# RGBdriver.net
KiCad netlist of a schematic drawn in EAGLE
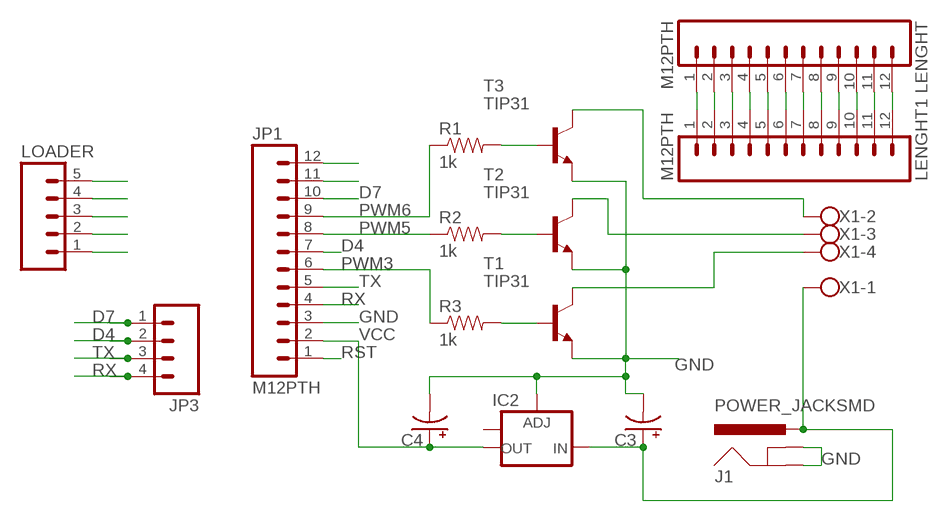
[diagram p0: schematic, sheet 1]

(export (version "E")
  (design (tool "Eeschema 10.0.6"))
  (components
    (comp (ref "C3")
      (value "CAP_POLC")
      (footprint "eagle-import:PANASONIC_C")
      (libsource (lib "eagle-import") (part "CAP_POLC"))
    )
    (comp (ref "C4")
      (value "CAP_POLC")
      (footprint "eagle-import:PANASONIC_C")
      (libsource (lib "eagle-import") (part "CAP_POLC"))
    )
    (comp (ref "IC2")
      (value "V_REG_LM1117SOT223")
      (footprint "eagle-import:SOT223")
      (libsource (lib "eagle-import") (part "V_REG_LM1117SOT223"))
    )
    (comp (ref "J1")
      (value "POWER_JACKSMD")
      (footprint "eagle-import:POWER_JACK_SMD")
      (libsource (lib "eagle-import") (part "POWER_JACKSMD"))
    )
    (comp (ref "JP1")
      (value "M12PTH")
      (footprint "eagle-import:1X12")
      (libsource (lib "eagle-import") (part "M12PTH"))
    )
    (comp (ref "JP3")
      (value "M04PTH")
      (footprint "eagle-import:1X04")
      (libsource (lib "eagle-import") (part "M04PTH"))
    )
    (comp (ref "LENGHT")
      (value "M12PTH")
      (footprint "eagle-import:1X12")
      (libsource (lib "eagle-import") (part "M12PTH"))
    )
    (comp (ref "LENGHT1")
      (value "M12PTH")
      (footprint "eagle-import:1X12")
      (libsource (lib "eagle-import") (part "M12PTH"))
    )
    (comp (ref "LOADER")
      (value "M05PTH")
      (footprint "eagle-import:1X05")
      (libsource (lib "eagle-import") (part "M05PTH"))
    )
    (comp (ref "R1")
      (value "1k")
      (footprint "eagle-import:1206")
      (libsource (lib "eagle-import") (part "RESISTOR1206"))
    )
    (comp (ref "R2")
      (value "1k")
      (footprint "eagle-import:1206")
      (libsource (lib "eagle-import") (part "RESISTOR1206"))
    )
    (comp (ref "R3")
      (value "1k")
      (footprint "eagle-import:1206")
      (libsource (lib "eagle-import") (part "RESISTOR1206"))
    )
    (comp (ref "T1")
      (value "TIP31")
      (footprint "eagle-import:TO220")
      (libsource (lib "eagle-import") (part "TIP31"))
    )
    (comp (ref "T2")
      (value "TIP31")
      (footprint "eagle-import:TO220")
      (libsource (lib "eagle-import") (part "TIP31"))
    )
    (comp (ref "T3")
      (value "TIP31")
      (footprint "eagle-import:TO220")
      (libsource (lib "eagle-import") (part "TIP31"))
    )
    (comp (ref "X1")
      (value "W237-4")
      (footprint "eagle-import:W237-4")
      (libsource (lib "eagle-import") (part "W237-4"))
    )
  )
  (nets
    (net (code "1") (name "/D4") (class "Default")
      (node (ref "JP1") (pin "7") (pinfunction "7_7") (pintype "passive"))
      (node (ref "JP3") (pin "2") (pinfunction "2_2") (pintype "passive"))
    )
    (net (code "2") (name "/D7") (class "Default")
      (node (ref "JP1") (pin "10") (pinfunction "10_10") (pintype "passive"))
      (node (ref "JP3") (pin "1") (pinfunction "1_1") (pintype "passive"))
    )
    (net (code "3") (name "/GND") (class "Default")
      (node (ref "C3") (pin "-") (pinfunction "-_-") (pintype "passive"))
      (node (ref "C4") (pin "-") (pinfunction "-_-") (pintype "passive"))
      (node (ref "IC2") (pin "1") (pinfunction "ADJ_1") (pintype "input"))
      (node (ref "J1") (pin "GND") (pinfunction "GNDBREAK_GND") (pintype "bidirectional"))
      (node (ref "J1") (pin "GNDBREAK") (pinfunction "GND_GNDBREAK") (pintype "bidirectional"))
      (node (ref "JP1") (pin "11") (pinfunction "11_11") (pintype "passive"))
      (node (ref "JP1") (pin "12") (pinfunction "12_12") (pintype "passive"))
      (node (ref "JP1") (pin "3") (pinfunction "3_3") (pintype "passive"))
      (node (ref "LENGHT") (pin "12") (pinfunction "12_12") (pintype "passive"))
      (node (ref "LENGHT") (pin "6") (pinfunction "6_6") (pintype "passive"))
      (node (ref "LENGHT1") (pin "12") (pinfunction "12_12") (pintype "passive"))
      (node (ref "LENGHT1") (pin "6") (pinfunction "6_6") (pintype "passive"))
      (node (ref "LOADER") (pin "3") (pinfunction "3_3") (pintype "passive"))
      (node (ref "T1") (pin "3") (pinfunction "E_3") (pintype "passive"))
      (node (ref "T2") (pin "3") (pinfunction "E_3") (pintype "passive"))
      (node (ref "T3") (pin "3") (pinfunction "E_3") (pintype "passive"))
    )
    (net (code "4") (name "/PWM3") (class "Default")
      (node (ref "JP1") (pin "6") (pinfunction "6_6") (pintype "passive"))
      (node (ref "R3") (pin "1") (pinfunction "1_1") (pintype "passive"))
    )
    (net (code "5") (name "/PWM5") (class "Default")
      (node (ref "JP1") (pin "8") (pinfunction "8_8") (pintype "passive"))
      (node (ref "R2") (pin "1") (pinfunction "1_1") (pintype "passive"))
    )
    (net (code "6") (name "/PWM6") (class "Default")
      (node (ref "JP1") (pin "9") (pinfunction "9_9") (pintype "passive"))
      (node (ref "R1") (pin "1") (pinfunction "1_1") (pintype "passive"))
    )
    (net (code "7") (name "/RST") (class "Default")
      (node (ref "JP1") (pin "1") (pinfunction "1_1") (pintype "passive"))
      (node (ref "LOADER") (pin "1") (pinfunction "1_1") (pintype "passive"))
    )
    (net (code "8") (name "/RX") (class "Default")
      (node (ref "JP1") (pin "4") (pinfunction "4_4") (pintype "passive"))
      (node (ref "JP3") (pin "4") (pinfunction "4_4") (pintype "passive"))
      (node (ref "LOADER") (pin "4") (pinfunction "4_4") (pintype "passive"))
    )
    (net (code "9") (name "/TX") (class "Default")
      (node (ref "JP1") (pin "5") (pinfunction "5_5") (pintype "passive"))
      (node (ref "JP3") (pin "3") (pinfunction "3_3") (pintype "passive"))
      (node (ref "LOADER") (pin "5") (pinfunction "5_5") (pintype "passive"))
    )
    (net (code "10") (name "/VCC") (class "Default")
      (node (ref "C4") (pin "+") (pinfunction "+_+") (pintype "passive"))
      (node (ref "IC2") (pin "2") (pinfunction "OUT_2") (pintype "output"))
      (node (ref "JP1") (pin "2") (pinfunction "2_2") (pintype "passive"))
      (node (ref "LOADER") (pin "2") (pinfunction "2_2") (pintype "passive"))
    )
    (net (code "11") (name "Net-(IC2-IN)") (class "Default")
      (node (ref "C3") (pin "+") (pinfunction "+_+") (pintype "passive"))
      (node (ref "IC2") (pin "3") (pinfunction "IN_3") (pintype "input"))
      (node (ref "J1") (pin "VIN0") (pinfunction "PWR_VIN0") (pintype "bidirectional"))
      (node (ref "X1") (pin "1") (pinfunction "KL_1") (pintype "passive"))
    )
    (net (code "12") (name "Net-(LENGHT-Pad1)") (class "Default")
      (node (ref "LENGHT") (pin "1") (pinfunction "1_1") (pintype "passive"))
      (node (ref "LENGHT1") (pin "1") (pinfunction "1_1") (pintype "passive"))
    )
    (net (code "13") (name "Net-(LENGHT-Pad2)") (class "Default")
      (node (ref "LENGHT") (pin "2") (pinfunction "2_2") (pintype "passive"))
      (node (ref "LENGHT1") (pin "2") (pinfunction "2_2") (pintype "passive"))
    )
    (net (code "14") (name "Net-(LENGHT-Pad3)") (class "Default")
      (node (ref "LENGHT") (pin "3") (pinfunction "3_3") (pintype "passive"))
      (node (ref "LENGHT1") (pin "3") (pinfunction "3_3") (pintype "passive"))
    )
    (net (code "15") (name "Net-(LENGHT-Pad4)") (class "Default")
      (node (ref "LENGHT") (pin "4") (pinfunction "4_4") (pintype "passive"))
      (node (ref "LENGHT1") (pin "4") (pinfunction "4_4") (pintype "passive"))
    )
    (net (code "16") (name "Net-(LENGHT-Pad5)") (class "Default")
      (node (ref "LENGHT") (pin "5") (pinfunction "5_5") (pintype "passive"))
      (node (ref "LENGHT1") (pin "5") (pinfunction "5_5") (pintype "passive"))
    )
    (net (code "17") (name "Net-(LENGHT-Pad7)") (class "Default")
      (node (ref "LENGHT") (pin "7") (pinfunction "7_7") (pintype "passive"))
      (node (ref "LENGHT1") (pin "7") (pinfunction "7_7") (pintype "passive"))
    )
    (net (code "18") (name "Net-(LENGHT-Pad8)") (class "Default")
      (node (ref "LENGHT") (pin "8") (pinfunction "8_8") (pintype "passive"))
      (node (ref "LENGHT1") (pin "8") (pinfunction "8_8") (pintype "passive"))
    )
    (net (code "19") (name "Net-(LENGHT-Pad9)") (class "Default")
      (node (ref "LENGHT") (pin "9") (pinfunction "9_9") (pintype "passive"))
      (node (ref "LENGHT1") (pin "9") (pinfunction "9_9") (pintype "passive"))
    )
    (net (code "20") (name "Net-(LENGHT-Pad10)") (class "Default")
      (node (ref "LENGHT") (pin "10") (pinfunction "10_10") (pintype "passive"))
      (node (ref "LENGHT1") (pin "10") (pinfunction "10_10") (pintype "passive"))
    )
    (net (code "21") (name "Net-(LENGHT-Pad11)") (class "Default")
      (node (ref "LENGHT") (pin "11") (pinfunction "11_11") (pintype "passive"))
      (node (ref "LENGHT1") (pin "11") (pinfunction "11_11") (pintype "passive"))
    )
    (net (code "22") (name "Net-(T1-B)") (class "Default")
      (node (ref "R3") (pin "2") (pinfunction "2_2") (pintype "passive"))
      (node (ref "T1") (pin "1") (pinfunction "B_1") (pintype "passive"))
    )
    (net (code "23") (name "Net-(T1-C)") (class "Default")
      (node (ref "T1") (pin "2") (pinfunction "C_2") (pintype "passive"))
      (node (ref "X1") (pin "4") (pinfunction "KL_4") (pintype "passive"))
    )
    (net (code "24") (name "Net-(T2-B)") (class "Default")
      (node (ref "R2") (pin "2") (pinfunction "2_2") (pintype "passive"))
      (node (ref "T2") (pin "1") (pinfunction "B_1") (pintype "passive"))
    )
    (net (code "25") (name "Net-(T2-C)") (class "Default")
      (node (ref "T2") (pin "2") (pinfunction "C_2") (pintype "passive"))
      (node (ref "X1") (pin "3") (pinfunction "KL_3") (pintype "passive"))
    )
    (net (code "26") (name "Net-(T3-B)") (class "Default")
      (node (ref "R1") (pin "2") (pinfunction "2_2") (pintype "passive"))
      (node (ref "T3") (pin "1") (pinfunction "B_1") (pintype "passive"))
    )
    (net (code "27") (name "Net-(T3-C)") (class "Default")
      (node (ref "T3") (pin "2") (pinfunction "C_2") (pintype "passive"))
      (node (ref "X1") (pin "2") (pinfunction "KL_2") (pintype "passive"))
    )
    (net (code "28") (name "unconnected-(IC2-OUT-Pad4)") (class "Default")
      (node (ref "IC2") (pin "4") (pinfunction "OUT_4") (pintype "output"))
    )
  )
)
